# main.net
KiCad netlist of a schematic drawn in EAGLE
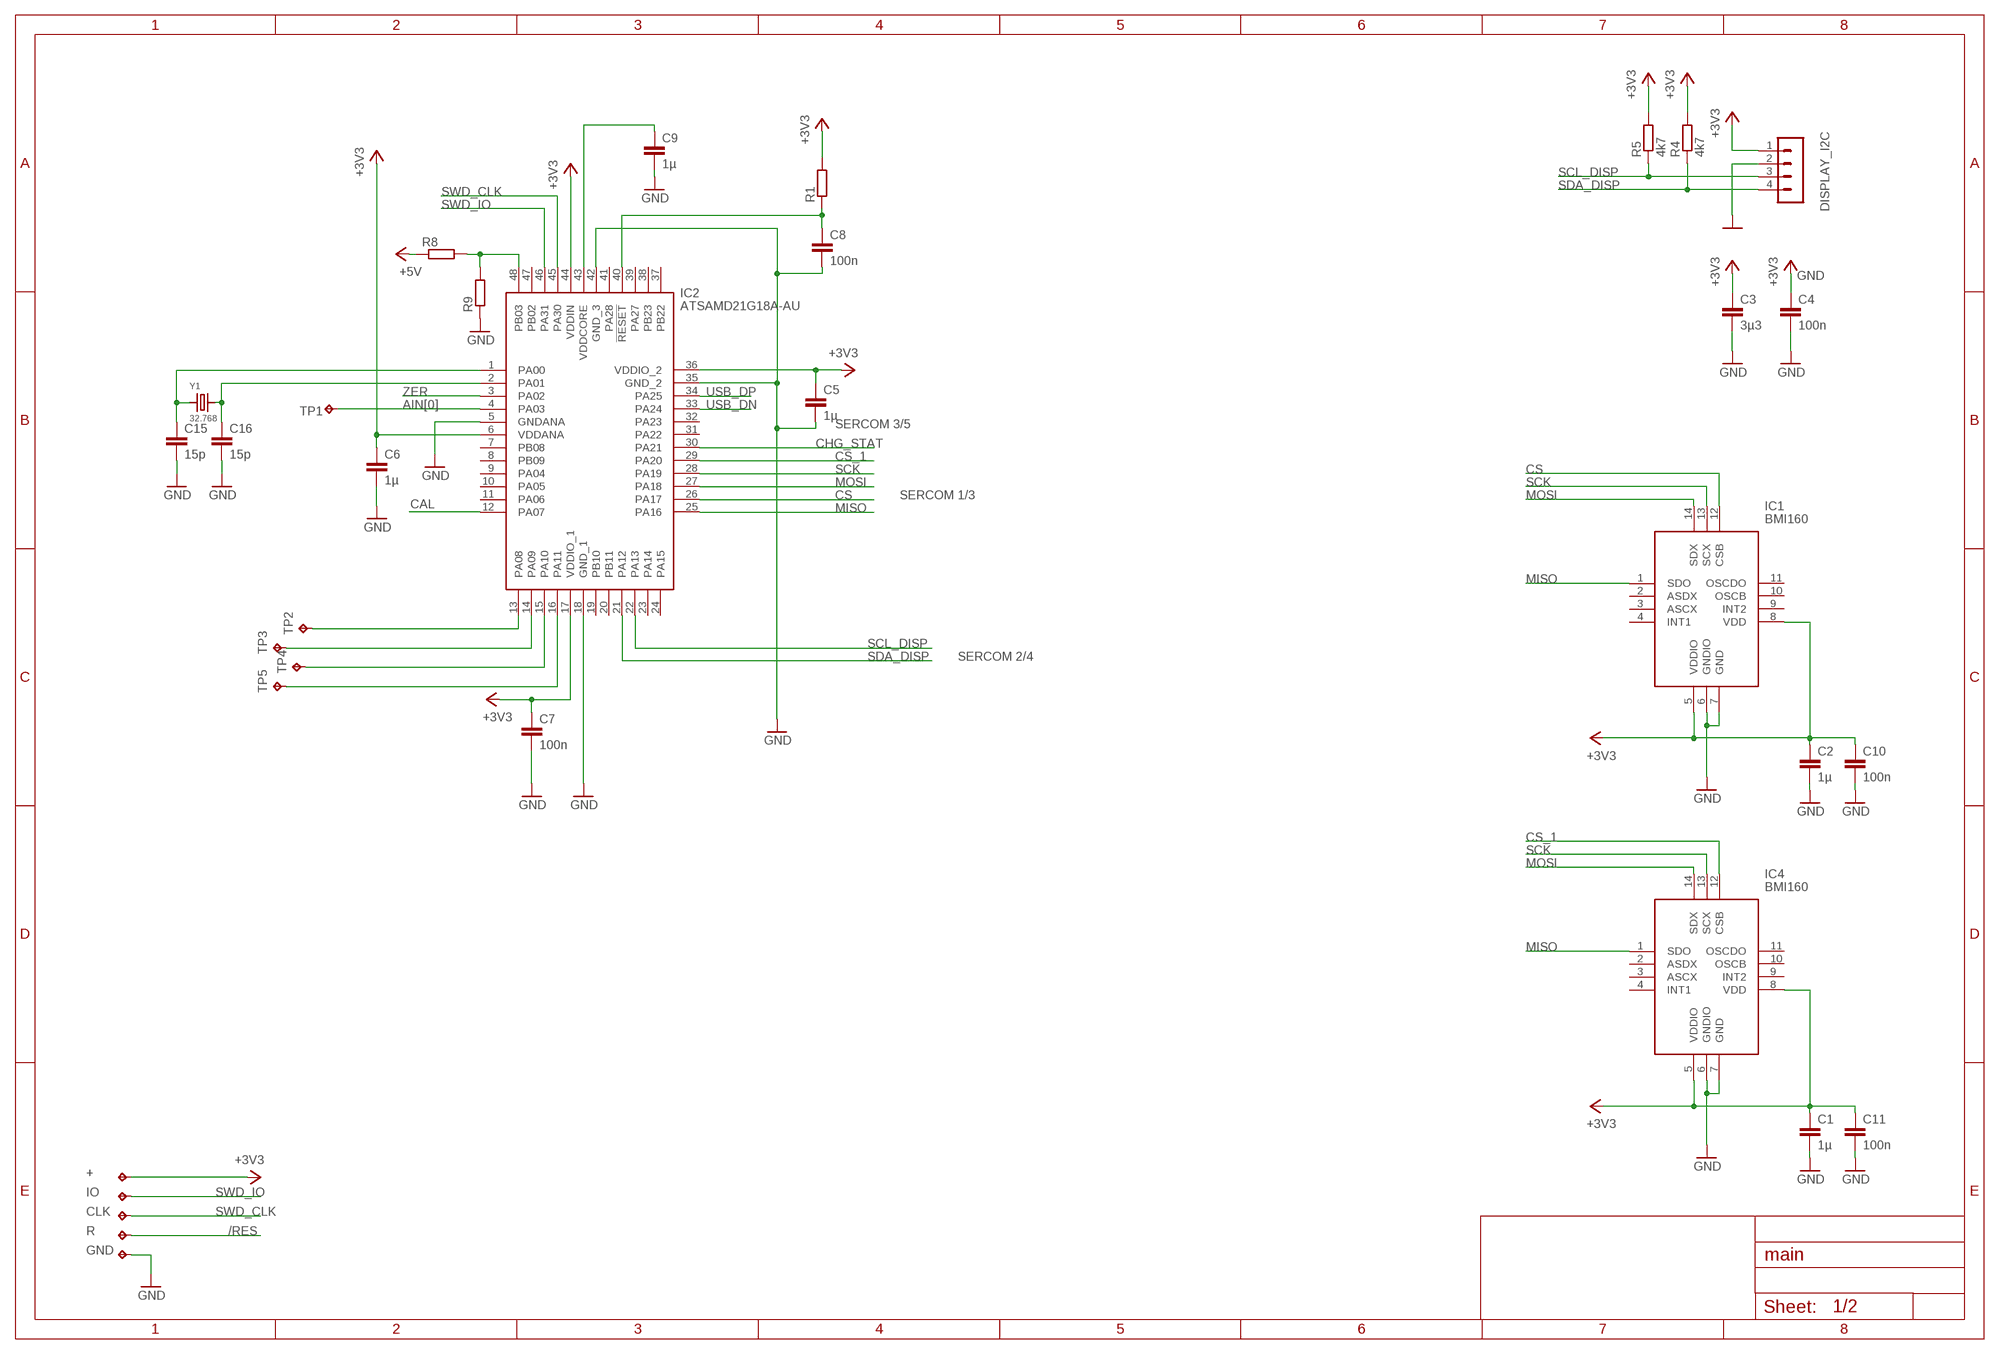
[diagram p0: schematic, sheet 1]
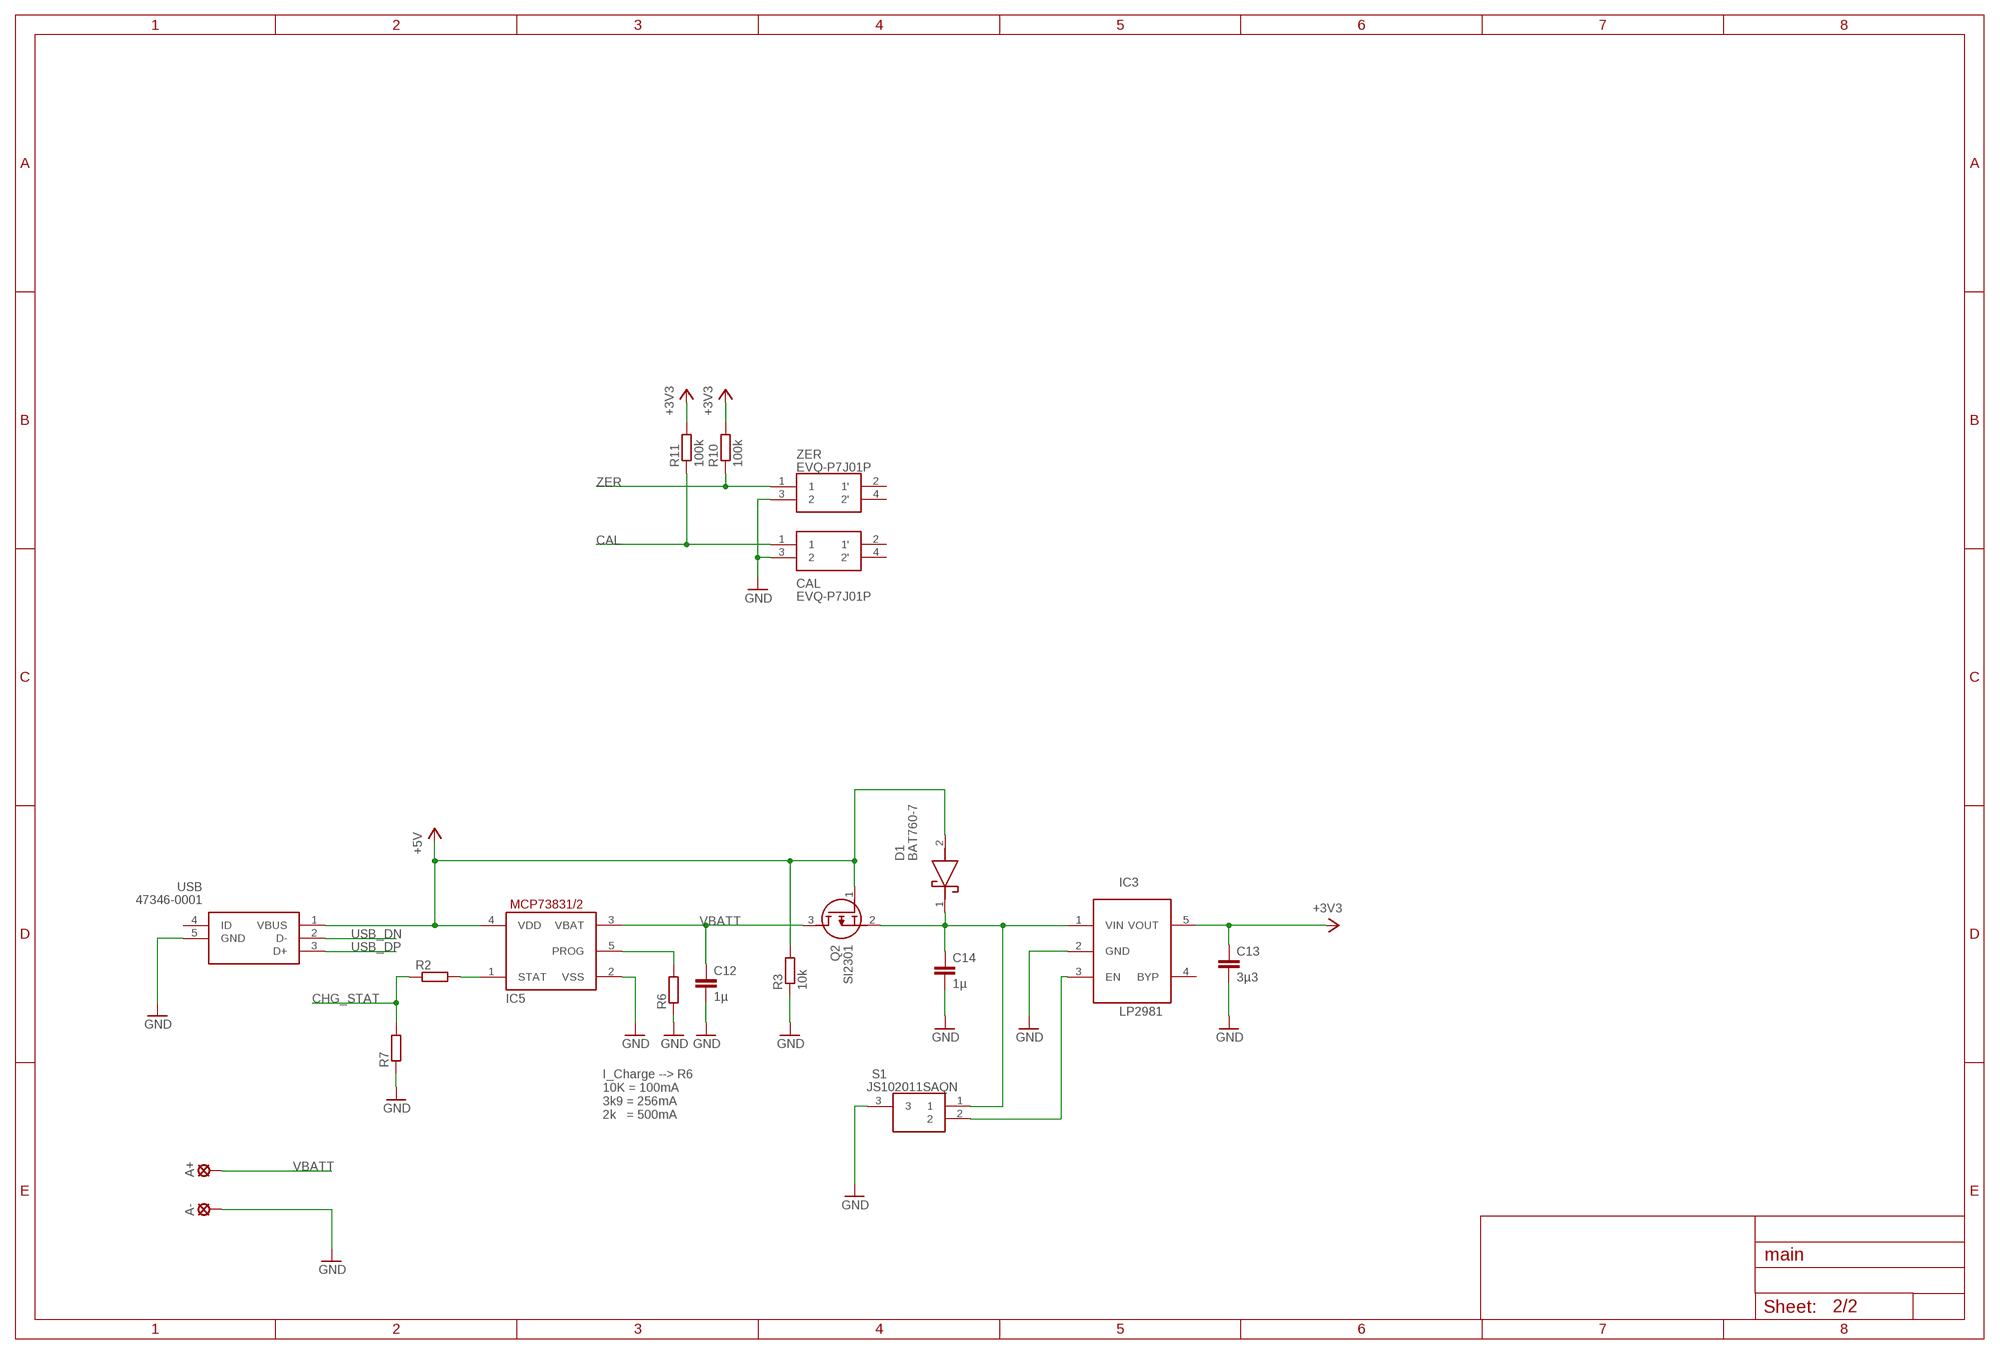
[diagram p1: schematic, sheet 2]

(export (version "E")
  (design (tool "Eeschema 10.0.6"))
  (components
    (comp (ref "+")
      (value "TPB1,27")
      (footprint "eagle-import:B1,27")
      (libsource (lib "eagle-import") (part "TPB1,27"))
    )
    (comp (ref "C1")
      (value "1µ")
      (footprint "eagle-import:C0402K")
      (libsource (lib "eagle-import") (part "C-EUC0402K"))
    )
    (comp (ref "C2")
      (value "1µ")
      (footprint "eagle-import:C0402K")
      (libsource (lib "eagle-import") (part "C-EUC0402K"))
    )
    (comp (ref "C3")
      (value "3µ3")
      (footprint "eagle-import:C0402K")
      (libsource (lib "eagle-import") (part "C-EUC0402K"))
    )
    (comp (ref "C4")
      (value "100n")
      (footprint "eagle-import:C0402K")
      (libsource (lib "eagle-import") (part "C-EUC0402K"))
    )
    (comp (ref "C5")
      (value "1µ")
      (footprint "eagle-import:C0402K")
      (libsource (lib "eagle-import") (part "C-EUC0402K"))
    )
    (comp (ref "C6")
      (value "1µ")
      (footprint "eagle-import:C0402K")
      (libsource (lib "eagle-import") (part "C-EUC0402K"))
    )
    (comp (ref "C7")
      (value "100n")
      (footprint "eagle-import:C0402K")
      (libsource (lib "eagle-import") (part "C-EUC0402K"))
    )
    (comp (ref "C8")
      (value "100n")
      (footprint "eagle-import:C0402K")
      (libsource (lib "eagle-import") (part "C-EUC0402K"))
    )
    (comp (ref "C9")
      (value "1µ")
      (footprint "eagle-import:C0402K")
      (libsource (lib "eagle-import") (part "C-EUC0402K"))
    )
    (comp (ref "C10")
      (value "100n")
      (footprint "eagle-import:C0402K")
      (libsource (lib "eagle-import") (part "C-EUC0402K"))
    )
    (comp (ref "C11")
      (value "100n")
      (footprint "eagle-import:C0402K")
      (libsource (lib "eagle-import") (part "C-EUC0402K"))
    )
    (comp (ref "C15")
      (value "15p")
      (footprint "eagle-import:C0402")
      (libsource (lib "eagle-import") (part "C-EUC0402"))
    )
    (comp (ref "C16")
      (value "15p")
      (footprint "eagle-import:C0402")
      (libsource (lib "eagle-import") (part "C-EUC0402"))
    )
    (comp (ref "CLK")
      (value "TPB1,27")
      (footprint "eagle-import:B1,27")
      (libsource (lib "eagle-import") (part "TPB1,27"))
    )
    (comp (ref "DISPLAY_I2C")
      (value "MA04-1")
      (footprint "eagle-import:MA04-1")
      (libsource (lib "eagle-import") (part "MA04-1"))
    )
    (comp (ref "GND")
      (value "TPB1,27")
      (footprint "eagle-import:B1,27")
      (libsource (lib "eagle-import") (part "TPB1,27"))
    )
    (comp (ref "IC1")
      (value "BMI160")
      (footprint "eagle-import:PQFN50P300X250X88-14N")
      (fields (field (name "MOUSER_PART_NUMBER") "262-BMI160"))
      (libsource (lib "eagle-import") (part "BMI160"))
    )
    (comp (ref "IC2")
      (value "ATSAMD21G18A-AU")
      (footprint "eagle-import:QFP50P900X900X120-48N")
      (fields
        (field (name "MOUSER_PART_NUMBER") "556-ATSAMD21G18A-AU")
        (field (name "RS_PART_NUMBER") "1773799P")
      )
      (libsource (lib "eagle-import") (part "ATSAMD21G18A-AU"))
    )
    (comp (ref "IC4")
      (value "BMI160")
      (footprint "eagle-import:PQFN50P300X250X88-14N")
      (fields (field (name "MOUSER_PART_NUMBER") "262-BMI160"))
      (libsource (lib "eagle-import") (part "BMI160"))
    )
    (comp (ref "IO")
      (value "TPB1,27")
      (footprint "eagle-import:B1,27")
      (libsource (lib "eagle-import") (part "TPB1,27"))
    )
    (comp (ref "R")
      (value "TPB1,27")
      (footprint "eagle-import:B1,27")
      (libsource (lib "eagle-import") (part "TPB1,27"))
    )
    (comp (ref "R1")
      (value "R-EU_R0402")
      (footprint "eagle-import:R0402")
      (libsource (lib "eagle-import") (part "R-EU_R0402"))
    )
    (comp (ref "R4")
      (value "4k7")
      (footprint "eagle-import:R0402")
      (libsource (lib "eagle-import") (part "R-EU_R0402"))
    )
    (comp (ref "R5")
      (value "4k7")
      (footprint "eagle-import:R0402")
      (libsource (lib "eagle-import") (part "R-EU_R0402"))
    )
    (comp (ref "R8")
      (value "R-EU_R0402")
      (footprint "eagle-import:R0402")
      (libsource (lib "eagle-import") (part "R-EU_R0402"))
    )
    (comp (ref "R9")
      (value "R-EU_R0402")
      (footprint "eagle-import:R0402")
      (libsource (lib "eagle-import") (part "R-EU_R0402"))
    )
    (comp (ref "TP1")
      (value "TPB1,27")
      (footprint "eagle-import:B1,27")
      (libsource (lib "eagle-import") (part "TPB1,27"))
    )
    (comp (ref "TP2")
      (value "TPB1,27")
      (footprint "eagle-import:B1,27")
      (libsource (lib "eagle-import") (part "TPB1,27"))
    )
    (comp (ref "TP3")
      (value "TPB1,27")
      (footprint "eagle-import:B1,27")
      (libsource (lib "eagle-import") (part "TPB1,27"))
    )
    (comp (ref "TP4")
      (value "TPB1,27")
      (footprint "eagle-import:B1,27")
      (libsource (lib "eagle-import") (part "TPB1,27"))
    )
    (comp (ref "TP5")
      (value "TPB1,27")
      (footprint "eagle-import:B1,27")
      (libsource (lib "eagle-import") (part "TPB1,27"))
    )
    (comp (ref "Y1")
      (value "32.768")
      (footprint "eagle-import:CRYSTAL_4.9X1.8")
      (libsource (lib "eagle-import") (part "CRYSTALTHIN32K"))
    )
    (comp (ref "A+")
      (value "MCS08")
      (footprint "eagle-import:MCS08")
      (libsource (lib "eagle-import") (part "MCS08"))
    )
    (comp (ref "A-")
      (value "MCS08")
      (footprint "eagle-import:MCS08")
      (libsource (lib "eagle-import") (part "MCS08"))
    )
    (comp (ref "C12")
      (value "1µ")
      (footprint "eagle-import:C0603")
      (libsource (lib "eagle-import") (part "C-EUC0603"))
    )
    (comp (ref "C13")
      (value "3µ3")
      (footprint "eagle-import:C0603")
      (libsource (lib "eagle-import") (part "C-EUC0603"))
    )
    (comp (ref "C14")
      (value "1µ")
      (footprint "eagle-import:C0603")
      (libsource (lib "eagle-import") (part "C-EUC0603"))
    )
    (comp (ref "CAL")
      (value "EVQ-P7J01P")
      (footprint "eagle-import:EVQP7J01P")
      (fields (field (name "MOUSER_PART_NUMBER") "667-EVQP7J01P"))
      (libsource (lib "eagle-import") (part "EVQ-P7J01P"))
    )
    (comp (ref "D1")
      (value "BAT760-7")
      (footprint "eagle-import:SOD2513X120N")
      (fields (field (name "MOUSER_PART_NUMBER") "621-BAT760-7"))
      (libsource (lib "eagle-import") (part "BAT760-7"))
    )
    (comp (ref "IC3")
      (value "LP2981")
      (footprint "eagle-import:SOT23-5L")
      (libsource (lib "eagle-import") (part "LP298XS"))
    )
    (comp (ref "IC5")
      (value "MCP73831/OT")
      (footprint "eagle-import:SOT23-5L")
      (libsource (lib "eagle-import") (part "MCP73831/OT"))
    )
    (comp (ref "Q2")
      (value "SI2301")
      (footprint "eagle-import:SOT95P240X120-3N")
      (libsource (lib "eagle-import") (part "SI2301"))
    )
    (comp (ref "R2")
      (value "R-EU_R0402")
      (footprint "eagle-import:R0402")
      (libsource (lib "eagle-import") (part "R-EU_R0402"))
    )
    (comp (ref "R3")
      (value "10k")
      (footprint "eagle-import:R0402")
      (libsource (lib "eagle-import") (part "R-EU_R0402"))
    )
    (comp (ref "R6")
      (value "R-EU_R0402")
      (footprint "eagle-import:R0402")
      (libsource (lib "eagle-import") (part "R-EU_R0402"))
    )
    (comp (ref "R7")
      (value "R-EU_R0402")
      (footprint "eagle-import:R0402")
      (libsource (lib "eagle-import") (part "R-EU_R0402"))
    )
    (comp (ref "R10")
      (value "100k")
      (footprint "eagle-import:R0402")
      (libsource (lib "eagle-import") (part "R-EU_R0402"))
    )
    (comp (ref "R11")
      (value "100k")
      (footprint "eagle-import:R0402")
      (libsource (lib "eagle-import") (part "R-EU_R0402"))
    )
    (comp (ref "S1")
      (value "JS102011SAQN")
      (footprint "eagle-import:JS102011SAQN")
      (fields (field (name "MOUSER_PART_NUMBER") "611-JS102011SAQN"))
      (libsource (lib "eagle-import") (part "JS102011SAQN"))
    )
    (comp (ref "USB")
      (value "47346-0001")
      (footprint "eagle-import:47346-0001")
      (fields (field (name "MOUSER_PART_NUMBER") "538-47346-0001"))
      (libsource (lib "eagle-import") (part "47346-0001"))
    )
    (comp (ref "ZER")
      (value "EVQ-P7J01P")
      (footprint "eagle-import:EVQP7J01P")
      (fields (field (name "MOUSER_PART_NUMBER") "667-EVQP7J01P"))
      (libsource (lib "eagle-import") (part "EVQ-P7J01P"))
    )
  )
  (nets
    (net (code "1") (name "+3V3") (class "Default")
      (node (ref "+") (pin "TP") (pinfunction "TP_TP") (pintype "input"))
      (node (ref "C1") (pin "1") (pinfunction "1_1") (pintype "passive"))
      (node (ref "C10") (pin "1") (pinfunction "1_1") (pintype "passive"))
      (node (ref "C11") (pin "1") (pinfunction "1_1") (pintype "passive"))
      (node (ref "C13") (pin "1") (pinfunction "1_1") (pintype "passive"))
      (node (ref "C2") (pin "1") (pinfunction "1_1") (pintype "passive"))
      (node (ref "C3") (pin "1") (pinfunction "1_1") (pintype "passive"))
      (node (ref "C4") (pin "1") (pinfunction "1_1") (pintype "passive"))
      (node (ref "C5") (pin "1") (pinfunction "1_1") (pintype "passive"))
      (node (ref "C6") (pin "1") (pinfunction "1_1") (pintype "passive"))
      (node (ref "C7") (pin "1") (pinfunction "1_1") (pintype "passive"))
      (node (ref "DISPLAY_I2C") (pin "1") (pinfunction "1_1") (pintype "passive"))
      (node (ref "IC1") (pin "5") (pinfunction "VDDIO_5") (pintype "power_in"))
      (node (ref "IC1") (pin "8") (pinfunction "VDD_8") (pintype "power_in"))
      (node (ref "IC2") (pin "17") (pinfunction "VDDIO_1_17") (pintype "bidirectional"))
      (node (ref "IC2") (pin "36") (pinfunction "VDDIO_2_36") (pintype "bidirectional"))
      (node (ref "IC2") (pin "44") (pinfunction "VDDIN_44") (pintype "bidirectional"))
      (node (ref "IC2") (pin "6") (pinfunction "VDDANA_6") (pintype "bidirectional"))
      (node (ref "IC3") (pin "5") (pinfunction "VOUT_5") (pintype "bidirectional"))
      (node (ref "IC4") (pin "5") (pinfunction "VDDIO_5") (pintype "power_in"))
      (node (ref "IC4") (pin "8") (pinfunction "VDD_8") (pintype "power_in"))
      (node (ref "R1") (pin "2") (pinfunction "2_2") (pintype "passive"))
      (node (ref "R10") (pin "2") (pinfunction "2_2") (pintype "passive"))
      (node (ref "R11") (pin "2") (pinfunction "2_2") (pintype "passive"))
      (node (ref "R4") (pin "2") (pinfunction "2_2") (pintype "passive"))
      (node (ref "R5") (pin "2") (pinfunction "2_2") (pintype "passive"))
    )
    (net (code "2") (name "+5V") (class "Default")
      (node (ref "D1") (pin "2") (pinfunction "A_2") (pintype "bidirectional"))
      (node (ref "IC5") (pin "4") (pinfunction "VDD_4") (pintype "power_in"))
      (node (ref "Q2") (pin "1") (pinfunction "G_1") (pintype "bidirectional"))
      (node (ref "R3") (pin "2") (pinfunction "2_2") (pintype "passive"))
      (node (ref "R8") (pin "1") (pinfunction "1_1") (pintype "passive"))
      (node (ref "USB") (pin "1") (pinfunction "VBUS_1") (pintype "bidirectional"))
    )
    (net (code "3") (name "AIN[0]") (class "Default")
      (node (ref "IC2") (pin "4") (pinfunction "PA03_4") (pintype "bidirectional"))
      (node (ref "TP1") (pin "TP") (pinfunction "TP_TP") (pintype "input"))
    )
    (net (code "4") (name "CAL") (class "Default")
      (node (ref "CAL") (pin "1") (pinfunction "1_1") (pintype "bidirectional"))
      (node (ref "IC2") (pin "12") (pinfunction "PA07_12") (pintype "bidirectional"))
      (node (ref "R11") (pin "1") (pinfunction "1_1") (pintype "passive"))
    )
    (net (code "5") (name "CHG_STAT") (class "Default")
      (node (ref "IC2") (pin "30") (pinfunction "PA21_30") (pintype "bidirectional"))
      (node (ref "R2") (pin "1") (pinfunction "1_1") (pintype "passive"))
      (node (ref "R7") (pin "2") (pinfunction "2_2") (pintype "passive"))
    )
    (net (code "6") (name "CS") (class "Default")
      (node (ref "IC1") (pin "12") (pinfunction "CSB_12") (pintype "input"))
      (node (ref "IC2") (pin "26") (pinfunction "PA17_26") (pintype "bidirectional"))
    )
    (net (code "7") (name "CS_1") (class "Default")
      (node (ref "IC2") (pin "29") (pinfunction "PA20_29") (pintype "bidirectional"))
      (node (ref "IC4") (pin "12") (pinfunction "CSB_12") (pintype "input"))
    )
    (net (code "8") (name "GND") (class "Default")
      (node (ref "A-") (pin "MP") (pinfunction "MP_MP") (pintype "passive"))
      (node (ref "C1") (pin "2") (pinfunction "2_2") (pintype "passive"))
      (node (ref "C10") (pin "2") (pinfunction "2_2") (pintype "passive"))
      (node (ref "C11") (pin "2") (pinfunction "2_2") (pintype "passive"))
      (node (ref "C12") (pin "2") (pinfunction "2_2") (pintype "passive"))
      (node (ref "C13") (pin "2") (pinfunction "2_2") (pintype "passive"))
      (node (ref "C14") (pin "2") (pinfunction "2_2") (pintype "passive"))
      (node (ref "C15") (pin "2") (pinfunction "2_2") (pintype "passive"))
      (node (ref "C16") (pin "2") (pinfunction "2_2") (pintype "passive"))
      (node (ref "C2") (pin "2") (pinfunction "2_2") (pintype "passive"))
      (node (ref "C3") (pin "2") (pinfunction "2_2") (pintype "passive"))
      (node (ref "C4") (pin "2") (pinfunction "2_2") (pintype "passive"))
      (node (ref "C5") (pin "2") (pinfunction "2_2") (pintype "passive"))
      (node (ref "C6") (pin "2") (pinfunction "2_2") (pintype "passive"))
      (node (ref "C7") (pin "2") (pinfunction "2_2") (pintype "passive"))
      (node (ref "C8") (pin "2") (pinfunction "2_2") (pintype "passive"))
      (node (ref "C9") (pin "2") (pinfunction "2_2") (pintype "passive"))
      (node (ref "CAL") (pin "3") (pinfunction "2_3") (pintype "bidirectional"))
      (node (ref "DISPLAY_I2C") (pin "2") (pinfunction "2_2") (pintype "passive"))
      (node (ref "GND") (pin "TP") (pinfunction "TP_TP") (pintype "input"))
      (node (ref "IC1") (pin "6") (pinfunction "GNDIO_6") (pintype "power_in"))
      (node (ref "IC1") (pin "7") (pinfunction "GND_7") (pintype "power_in"))
      (node (ref "IC2") (pin "18") (pinfunction "GND_1_18") (pintype "bidirectional"))
      (node (ref "IC2") (pin "35") (pinfunction "GND_2_35") (pintype "bidirectional"))
      (node (ref "IC2") (pin "42") (pinfunction "GND_3_42") (pintype "bidirectional"))
      (node (ref "IC2") (pin "5") (pinfunction "GNDANA_5") (pintype "bidirectional"))
      (node (ref "IC3") (pin "2") (pinfunction "GND_2") (pintype "bidirectional"))
      (node (ref "IC4") (pin "6") (pinfunction "GNDIO_6") (pintype "power_in"))
      (node (ref "IC4") (pin "7") (pinfunction "GND_7") (pintype "power_in"))
      (node (ref "IC5") (pin "2") (pinfunction "VSS_2") (pintype "power_in"))
      (node (ref "R3") (pin "1") (pinfunction "1_1") (pintype "passive"))
      (node (ref "R6") (pin "1") (pinfunction "1_1") (pintype "passive"))
      (node (ref "R7") (pin "1") (pinfunction "1_1") (pintype "passive"))
      (node (ref "R9") (pin "1") (pinfunction "1_1") (pintype "passive"))
      (node (ref "S1") (pin "3") (pinfunction "3_3") (pintype "bidirectional"))
      (node (ref "USB") (pin "5") (pinfunction "GND_5") (pintype "bidirectional"))
      (node (ref "ZER") (pin "3") (pinfunction "2_3") (pintype "bidirectional"))
    )
    (net (code "9") (name "MISO") (class "Default")
      (node (ref "IC1") (pin "1") (pinfunction "SDO_1") (pintype "bidirectional"))
      (node (ref "IC2") (pin "25") (pinfunction "PA16_25") (pintype "bidirectional"))
      (node (ref "IC4") (pin "1") (pinfunction "SDO_1") (pintype "bidirectional"))
    )
    (net (code "10") (name "MOSI") (class "Default")
      (node (ref "IC1") (pin "14") (pinfunction "SDX_14") (pintype "bidirectional"))
      (node (ref "IC2") (pin "27") (pinfunction "PA18_27") (pintype "bidirectional"))
      (node (ref "IC4") (pin "14") (pinfunction "SDX_14") (pintype "bidirectional"))
    )
    (net (code "11") (name "Net-(D1-K)") (class "Default")
      (node (ref "C14") (pin "1") (pinfunction "1_1") (pintype "passive"))
      (node (ref "D1") (pin "1") (pinfunction "K_1") (pintype "bidirectional"))
      (node (ref "IC3") (pin "1") (pinfunction "VIN_1") (pintype "bidirectional"))
      (node (ref "Q2") (pin "2") (pinfunction "S_2") (pintype "bidirectional"))
      (node (ref "S1") (pin "1") (pinfunction "1_1") (pintype "bidirectional"))
    )
    (net (code "12") (name "Net-(IC2-PA00)") (class "Default")
      (node (ref "C15") (pin "1") (pinfunction "1_1") (pintype "passive"))
      (node (ref "IC2") (pin "1") (pinfunction "PA00_1") (pintype "bidirectional"))
      (node (ref "Y1") (pin "1") (pinfunction "1_1") (pintype "passive"))
    )
    (net (code "13") (name "Net-(IC2-PA01)") (class "Default")
      (node (ref "C16") (pin "1") (pinfunction "1_1") (pintype "passive"))
      (node (ref "IC2") (pin "2") (pinfunction "PA01_2") (pintype "bidirectional"))
      (node (ref "Y1") (pin "2") (pinfunction "2_2") (pintype "passive"))
    )
    (net (code "14") (name "Net-(IC2-PA08)") (class "Default")
      (node (ref "IC2") (pin "13") (pinfunction "PA08_13") (pintype "bidirectional"))
      (node (ref "TP2") (pin "TP") (pinfunction "TP_TP") (pintype "input"))
    )
    (net (code "15") (name "Net-(IC2-PA09)") (class "Default")
      (node (ref "IC2") (pin "14") (pinfunction "PA09_14") (pintype "bidirectional"))
      (node (ref "TP3") (pin "TP") (pinfunction "TP_TP") (pintype "input"))
    )
    (net (code "16") (name "Net-(IC2-PA10)") (class "Default")
      (node (ref "IC2") (pin "15") (pinfunction "PA10_15") (pintype "bidirectional"))
      (node (ref "TP4") (pin "TP") (pinfunction "TP_TP") (pintype "input"))
    )
    (net (code "17") (name "Net-(IC2-PA11)") (class "Default")
      (node (ref "IC2") (pin "16") (pinfunction "PA11_16") (pintype "bidirectional"))
      (node (ref "TP5") (pin "TP") (pinfunction "TP_TP") (pintype "input"))
    )
    (net (code "18") (name "Net-(IC2-PB03)") (class "Default")
      (node (ref "IC2") (pin "48") (pinfunction "PB03_48") (pintype "bidirectional"))
      (node (ref "R8") (pin "2") (pinfunction "2_2") (pintype "passive"))
      (node (ref "R9") (pin "2") (pinfunction "2_2") (pintype "passive"))
    )
    (net (code "19") (name "Net-(IC2-VDDCORE)") (class "Default")
      (node (ref "C9") (pin "1") (pinfunction "1_1") (pintype "passive"))
      (node (ref "IC2") (pin "43") (pinfunction "VDDCORE_43") (pintype "bidirectional"))
    )
    (net (code "20") (name "Net-(IC3-EN)") (class "Default")
      (node (ref "IC3") (pin "3") (pinfunction "EN_3") (pintype "bidirectional"))
      (node (ref "S1") (pin "2") (pinfunction "2_2") (pintype "bidirectional"))
    )
    (net (code "21") (name "Net-(IC5-PROG)") (class "Default")
      (node (ref "IC5") (pin "5") (pinfunction "PROG_5") (pintype "input"))
      (node (ref "R6") (pin "2") (pinfunction "2_2") (pintype "passive"))
    )
    (net (code "22") (name "Net-(IC5-STAT)") (class "Default")
      (node (ref "IC5") (pin "1") (pinfunction "STAT_1") (pintype "output"))
      (node (ref "R2") (pin "2") (pinfunction "2_2") (pintype "passive"))
    )
    (net (code "23") (name "SCK") (class "Default")
      (node (ref "IC1") (pin "13") (pinfunction "SCX_13") (pintype "bidirectional"))
      (node (ref "IC2") (pin "28") (pinfunction "PA19_28") (pintype "bidirectional"))
      (node (ref "IC4") (pin "13") (pinfunction "SCX_13") (pintype "bidirectional"))
    )
    (net (code "24") (name "SCL_DISP") (class "Default")
      (node (ref "DISPLAY_I2C") (pin "3") (pinfunction "3_3") (pintype "passive"))
      (node (ref "IC2") (pin "22") (pinfunction "PA13_22") (pintype "bidirectional"))
      (node (ref "R5") (pin "1") (pinfunction "1_1") (pintype "passive"))
    )
    (net (code "25") (name "SDA_DISP") (class "Default")
      (node (ref "DISPLAY_I2C") (pin "4") (pinfunction "4_4") (pintype "passive"))
      (node (ref "IC2") (pin "21") (pinfunction "PA12_21") (pintype "bidirectional"))
      (node (ref "R4") (pin "1") (pinfunction "1_1") (pintype "passive"))
    )
    (net (code "26") (name "SWD_CLK") (class "Default")
      (node (ref "CLK") (pin "TP") (pinfunction "TP_TP") (pintype "input"))
      (node (ref "IC2") (pin "45") (pinfunction "PA30_45") (pintype "bidirectional"))
    )
    (net (code "27") (name "SWD_IO") (class "Default")
      (node (ref "IC2") (pin "46") (pinfunction "PA31_46") (pintype "bidirectional"))
      (node (ref "IO") (pin "TP") (pinfunction "TP_TP") (pintype "input"))
    )
    (net (code "28") (name "USB_DN") (class "Default")
      (node (ref "IC2") (pin "33") (pinfunction "PA24_33") (pintype "bidirectional"))
      (node (ref "USB") (pin "2") (pinfunction "D-_2") (pintype "bidirectional"))
    )
    (net (code "29") (name "USB_DP") (class "Default")
      (node (ref "IC2") (pin "34") (pinfunction "PA25_34") (pintype "bidirectional"))
      (node (ref "USB") (pin "3") (pinfunction "D+_3") (pintype "bidirectional"))
    )
    (net (code "30") (name "VBATT") (class "Default")
      (node (ref "A+") (pin "MP") (pinfunction "MP_MP") (pintype "passive"))
      (node (ref "C12") (pin "1") (pinfunction "1_1") (pintype "passive"))
      (node (ref "IC5") (pin "3") (pinfunction "VBAT_3") (pintype "bidirectional"))
      (node (ref "Q2") (pin "3") (pinfunction "D_3") (pintype "bidirectional"))
    )
    (net (code "31") (name "ZER") (class "Default")
      (node (ref "IC2") (pin "3") (pinfunction "PA02_3") (pintype "bidirectional"))
      (node (ref "R10") (pin "1") (pinfunction "1_1") (pintype "passive"))
      (node (ref "ZER") (pin "1") (pinfunction "1_1") (pintype "bidirectional"))
    )
    (net (code "32") (name "unconnected-(CAL-1'-Pad2)") (class "Default")
      (node (ref "CAL") (pin "2") (pinfunction "1'_2") (pintype "bidirectional"))
    )
    (net (code "33") (name "unconnected-(CAL-2'-Pad4)") (class "Default")
      (node (ref "CAL") (pin "4") (pinfunction "2'_4") (pintype "bidirectional"))
    )
    (net (code "34") (name "unconnected-(IC1-ASCX-Pad3)") (class "Default")
      (node (ref "IC1") (pin "3") (pinfunction "ASCX_3") (pintype "bidirectional"))
    )
    (net (code "35") (name "unconnected-(IC1-ASDX-Pad2)") (class "Default")
      (node (ref "IC1") (pin "2") (pinfunction "ASDX_2") (pintype "bidirectional"))
    )
    (net (code "36") (name "unconnected-(IC1-INT1-Pad4)") (class "Default")
      (node (ref "IC1") (pin "4") (pinfunction "INT1_4") (pintype "input"))
    )
    (net (code "37") (name "unconnected-(IC1-INT2-Pad9)") (class "Default")
      (node (ref "IC1") (pin "9") (pinfunction "INT2_9") (pintype "input"))
    )
    (net (code "38") (name "unconnected-(IC1-OSCB-Pad10)") (class "Default")
      (node (ref "IC1") (pin "10") (pinfunction "OSCB_10") (pintype "bidirectional"))
    )
    (net (code "39") (name "unconnected-(IC1-OSCDO-Pad11)") (class "Default")
      (node (ref "IC1") (pin "11") (pinfunction "OSCDO_11") (pintype "bidirectional"))
    )
    (net (code "40") (name "unconnected-(IC2-PA04-Pad9)") (class "Default")
      (node (ref "IC2") (pin "9") (pinfunction "PA04_9") (pintype "bidirectional"))
    )
    (net (code "41") (name "unconnected-(IC2-PA05-Pad10)") (class "Default")
      (node (ref "IC2") (pin "10") (pinfunction "PA05_10") (pintype "bidirectional"))
    )
    (net (code "42") (name "unconnected-(IC2-PA06-Pad11)") (class "Default")
      (node (ref "IC2") (pin "11") (pinfunction "PA06_11") (pintype "bidirectional"))
    )
    (net (code "43") (name "unconnected-(IC2-PA14-Pad23)") (class "Default")
      (node (ref "IC2") (pin "23") (pinfunction "PA14_23") (pintype "bidirectional"))
    )
    (net (code "44") (name "unconnected-(IC2-PA15-Pad24)") (class "Default")
      (node (ref "IC2") (pin "24") (pinfunction "PA15_24") (pintype "bidirectional"))
    )
    (net (code "45") (name "unconnected-(IC2-PA22-Pad31)") (class "Default")
      (node (ref "IC2") (pin "31") (pinfunction "PA22_31") (pintype "bidirectional"))
    )
    (net (code "46") (name "unconnected-(IC2-PA23-Pad32)") (class "Default")
      (node (ref "IC2") (pin "32") (pinfunction "PA23_32") (pintype "bidirectional"))
    )
    (net (code "47") (name "unconnected-(IC2-PA27-Pad39)") (class "Default")
      (node (ref "IC2") (pin "39") (pinfunction "PA27_39") (pintype "bidirectional"))
    )
    (net (code "48") (name "unconnected-(IC2-PA28-Pad41)") (class "Default")
      (node (ref "IC2") (pin "41") (pinfunction "PA28_41") (pintype "bidirectional"))
    )
    (net (code "49") (name "unconnected-(IC2-PB02-Pad47)") (class "Default")
      (node (ref "IC2") (pin "47") (pinfunction "PB02_47") (pintype "bidirectional"))
    )
    (net (code "50") (name "unconnected-(IC2-PB08-Pad7)") (class "Default")
      (node (ref "IC2") (pin "7") (pinfunction "PB08_7") (pintype "bidirectional"))
    )
    (net (code "51") (name "unconnected-(IC2-PB09-Pad8)") (class "Default")
      (node (ref "IC2") (pin "8") (pinfunction "PB09_8") (pintype "bidirectional"))
    )
    (net (code "52") (name "unconnected-(IC2-PB10-Pad19)") (class "Default")
      (node (ref "IC2") (pin "19") (pinfunction "PB10_19") (pintype "bidirectional"))
    )
    (net (code "53") (name "unconnected-(IC2-PB11-Pad20)") (class "Default")
      (node (ref "IC2") (pin "20") (pinfunction "PB11_20") (pintype "bidirectional"))
    )
    (net (code "54") (name "unconnected-(IC2-PB22-Pad37)") (class "Default")
      (node (ref "IC2") (pin "37") (pinfunction "PB22_37") (pintype "bidirectional"))
    )
    (net (code "55") (name "unconnected-(IC2-PB23-Pad38)") (class "Default")
      (node (ref "IC2") (pin "38") (pinfunction "PB23_38") (pintype "bidirectional"))
    )
    (net (code "56") (name "unconnected-(IC3-BYP-Pad4)") (class "Default")
      (node (ref "IC3") (pin "4") (pinfunction "BYP_4") (pintype "bidirectional"))
    )
    (net (code "57") (name "unconnected-(IC4-ASCX-Pad3)") (class "Default")
      (node (ref "IC4") (pin "3") (pinfunction "ASCX_3") (pintype "bidirectional"))
    )
    (net (code "58") (name "unconnected-(IC4-ASDX-Pad2)") (class "Default")
      (node (ref "IC4") (pin "2") (pinfunction "ASDX_2") (pintype "bidirectional"))
    )
    (net (code "59") (name "unconnected-(IC4-INT1-Pad4)") (class "Default")
      (node (ref "IC4") (pin "4") (pinfunction "INT1_4") (pintype "input"))
    )
    (net (code "60") (name "unconnected-(IC4-INT2-Pad9)") (class "Default")
      (node (ref "IC4") (pin "9") (pinfunction "INT2_9") (pintype "input"))
    )
    (net (code "61") (name "unconnected-(IC4-OSCB-Pad10)") (class "Default")
      (node (ref "IC4") (pin "10") (pinfunction "OSCB_10") (pintype "bidirectional"))
    )
    (net (code "62") (name "unconnected-(IC4-OSCDO-Pad11)") (class "Default")
      (node (ref "IC4") (pin "11") (pinfunction "OSCDO_11") (pintype "bidirectional"))
    )
    (net (code "63") (name "unconnected-(USB-ID-Pad4)") (class "Default")
      (node (ref "USB") (pin "4") (pinfunction "ID_4") (pintype "bidirectional"))
    )
    (net (code "64") (name "unconnected-(ZER-1'-Pad2)") (class "Default")
      (node (ref "ZER") (pin "2") (pinfunction "1'_2") (pintype "bidirectional"))
    )
    (net (code "65") (name "unconnected-(ZER-2'-Pad4)") (class "Default")
      (node (ref "ZER") (pin "4") (pinfunction "2'_4") (pintype "bidirectional"))
    )
    (net (code "66") (name "{slash}RES") (class "Default")
      (node (ref "C8") (pin "1") (pinfunction "1_1") (pintype "passive"))
      (node (ref "IC2") (pin "40") (pinfunction "~{RESET}_40") (pintype "bidirectional"))
      (node (ref "R") (pin "TP") (pinfunction "TP_TP") (pintype "input"))
      (node (ref "R1") (pin "1") (pinfunction "1_1") (pintype "passive"))
    )
  )
)
